# Sheet1.net
KiCad netlist of a schematic drawn in Altium Designer
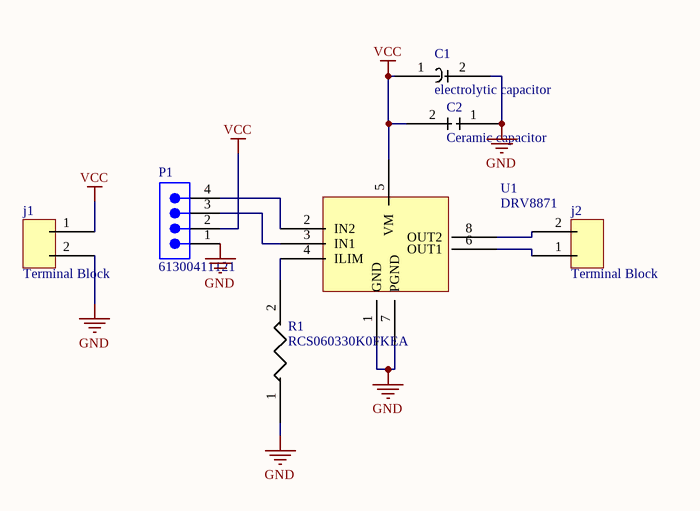
[diagram p0: Sheet1.SchDoc]

(export (version "E")
  (design (tool "Eeschema 10.0.6"))
  (components
    (comp (ref "C1")
      (value "electrolytic capacitor")
      (footprint "electrolytic capacitor")
      (fields
        (field (name "PART NUMBER") "732-8416-2-ND")
        (field (name "MANF") "Würth Elektronik")
        (field (name "MANF PART NUMBER") "865080342006")
      )
      (libsource (lib "Schlib1") (part "electrolytic capacitor"))
    )
    (comp (ref "C2")
      (value "Ceramic capacitor")
      (footprint "ceramic capacitor")
      (fields
        (field (name "PART NUMBER") "1276-1002-2-ND")
        (field (name "MANF") "Samsung Electro-Mechanics")
        (field (name "MANF PART NUMBER") "CL05B104KP5NNNC")
      )
      (libsource (lib "Schlib1") (part "Ceramic capacitor"))
    )
    (comp (ref "j1")
      (value "Terminal Block")
      (footprint "Terminal block")
      (fields (field (name "PART NUMBER") "300000007278"))
      (libsource (lib "Schlib1") (part "Terminal Block"))
    )
    (comp (ref "j2")
      (value "Terminal Block")
      (footprint "Terminal block")
      (fields (field (name "PART NUMBER") "300000007278"))
      (libsource (lib "") (part "Terminal Block_1"))
    )
    (comp (ref "P1")
      (value "61300411121")
      (footprint "61300411121")
      (libsource (lib "Altium Content Vault") (part "Header_Male_1R_04P"))
    )
    (comp (ref "R1")
      (value "RCS060330K0FKEA")
      (footprint "RCS060330K0FKEA")
      (fields (field (name "PART NUMBER") "541-10453-2-ND") (field (name "MANF") "Vishay Dale"))
      (libsource (lib "Schlib1") (part "RCS060330K0FKEA"))
    )
    (comp (ref "U1")
      (value "DRV8871")
      (footprint "DRV8871")
      (fields
        (field (name "PART NUMBER") "296-43024-2-ND")
        (field (name "MANFACTURER PART NUMBER") "DRV8871DDAR")
      )
      (libsource (lib "Schlib1") (part "DRV8871"))
    )
  )
  (nets
    (net (code "1") (name "GND") (class "Default")
      (node (ref "C1") (pin "2") (pintype "passive"))
      (node (ref "C2") (pin "1") (pintype "passive"))
      (node (ref "P1") (pin "1") (pinfunction "1_1") (pintype "passive"))
      (node (ref "R1") (pin "1") (pintype "passive"))
      (node (ref "U1") (pin "1") (pinfunction "GND_1") (pintype "passive"))
      (node (ref "U1") (pin "7") (pinfunction "PGND_7") (pintype "passive"))
      (node (ref "j1") (pin "2") (pintype "passive"))
    )
    (net (code "2") (name "Net-(U1-ILIM)") (class "Default")
      (node (ref "R1") (pin "2") (pintype "passive"))
      (node (ref "U1") (pin "4") (pinfunction "ILIM_4") (pintype "passive"))
    )
    (net (code "3") (name "Net-(U1-IN1)") (class "Default")
      (node (ref "P1") (pin "3") (pinfunction "3_3") (pintype "passive"))
      (node (ref "U1") (pin "3") (pinfunction "IN1_3") (pintype "passive"))
    )
    (net (code "4") (name "Net-(U1-IN2)") (class "Default")
      (node (ref "P1") (pin "4") (pinfunction "4_4") (pintype "passive"))
      (node (ref "U1") (pin "2") (pinfunction "IN2_2") (pintype "passive"))
    )
    (net (code "5") (name "Net-(U1-OUT1)") (class "Default")
      (node (ref "U1") (pin "6") (pinfunction "OUT1_6") (pintype "passive"))
      (node (ref "j2") (pin "1") (pintype "passive"))
    )
    (net (code "6") (name "Net-(U1-OUT2)") (class "Default")
      (node (ref "U1") (pin "8") (pinfunction "OUT2_8") (pintype "passive"))
      (node (ref "j2") (pin "2") (pintype "passive"))
    )
    (net (code "7") (name "VCC") (class "Default")
      (node (ref "C1") (pin "1") (pintype "passive"))
      (node (ref "C2") (pin "2") (pintype "passive"))
      (node (ref "P1") (pin "2") (pinfunction "2_2") (pintype "passive"))
      (node (ref "U1") (pin "5") (pinfunction "VM_5") (pintype "passive"))
      (node (ref "j1") (pin "1") (pintype "passive"))
    )
  )
)
